# untitled.net
KiCad netlist of a schematic drawn in EAGLE
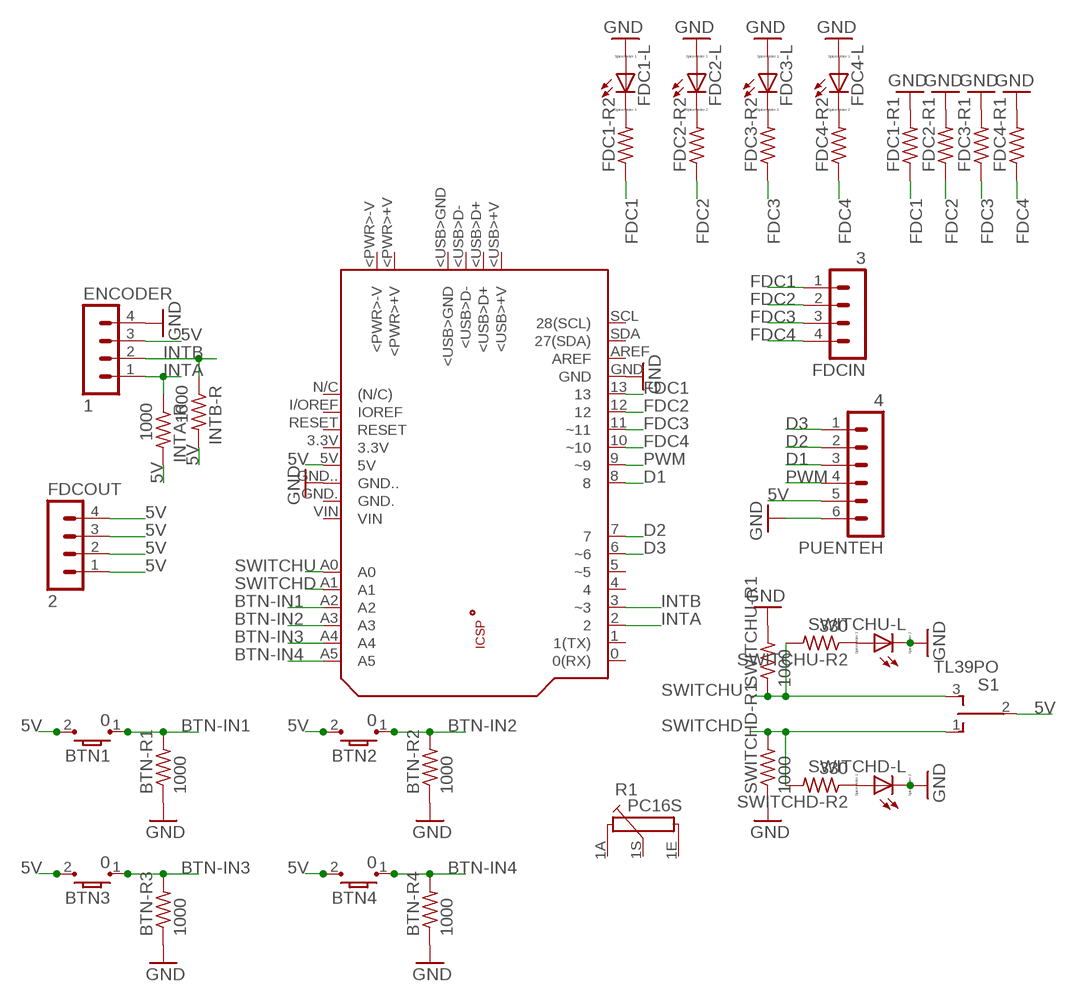
[diagram p0: schematic, sheet 1]

(export (version "E")
  (design (tool "Eeschema 10.0.6"))
  (components
    (comp (ref "BTN-R1")
      (value "1000")
      (footprint "eagle-import:0204_7")
      (libsource (lib "eagle-import") (part "R-US_0204/7"))
    )
    (comp (ref "BTN-R2")
      (value "1000")
      (footprint "eagle-import:0204_7")
      (libsource (lib "eagle-import") (part "R-US_0204/7"))
    )
    (comp (ref "BTN-R3")
      (value "1000")
      (footprint "eagle-import:0204_7")
      (libsource (lib "eagle-import") (part "R-US_0204/7"))
    )
    (comp (ref "BTN-R4")
      (value "1000")
      (footprint "eagle-import:0204_7")
      (libsource (lib "eagle-import") (part "R-US_0204/7"))
    )
    (comp (ref "BTN1")
      (value "0")
      (footprint "eagle-import:TL3303_J")
      (libsource (lib "eagle-import") (part "TL3302-J"))
    )
    (comp (ref "BTN2")
      (value "0")
      (footprint "eagle-import:TL3303_J")
      (libsource (lib "eagle-import") (part "TL3302-J"))
    )
    (comp (ref "BTN3")
      (value "0")
      (footprint "eagle-import:TL3303_J")
      (libsource (lib "eagle-import") (part "TL3302-J"))
    )
    (comp (ref "BTN4")
      (value "0")
      (footprint "eagle-import:TL3303_J")
      (libsource (lib "eagle-import") (part "TL3302-J"))
    )
    (comp (ref "ENCODER")
      (value "1")
      (footprint "eagle-import:MA04-1")
      (libsource (lib "eagle-import") (part "MA04-1"))
    )
    (comp (ref "FDC1-L")
      (value "LED_ELD260")
      (footprint "eagle-import:LED_LD260")
      (libsource (lib "eagle-import") (part "LED_ELD260"))
    )
    (comp (ref "FDC1-R1")
      (value "R-US_0204/7")
      (footprint "eagle-import:0204_7")
      (libsource (lib "eagle-import") (part "R-US_0204/7"))
    )
    (comp (ref "FDC1-R2")
      (value "R-US_0204/7")
      (footprint "eagle-import:0204_7")
      (libsource (lib "eagle-import") (part "R-US_0204/7"))
    )
    (comp (ref "FDC2-L")
      (value "LED_ELD260")
      (footprint "eagle-import:LED_LD260")
      (libsource (lib "eagle-import") (part "LED_ELD260"))
    )
    (comp (ref "FDC2-R1")
      (value "R-US_0204/7")
      (footprint "eagle-import:0204_7")
      (libsource (lib "eagle-import") (part "R-US_0204/7"))
    )
    (comp (ref "FDC2-R2")
      (value "R-US_0204/7")
      (footprint "eagle-import:0204_7")
      (libsource (lib "eagle-import") (part "R-US_0204/7"))
    )
    (comp (ref "FDC3-L")
      (value "LED_ELD260")
      (footprint "eagle-import:LED_LD260")
      (libsource (lib "eagle-import") (part "LED_ELD260"))
    )
    (comp (ref "FDC3-R1")
      (value "R-US_0204/7")
      (footprint "eagle-import:0204_7")
      (libsource (lib "eagle-import") (part "R-US_0204/7"))
    )
    (comp (ref "FDC3-R2")
      (value "R-US_0204/7")
      (footprint "eagle-import:0204_7")
      (libsource (lib "eagle-import") (part "R-US_0204/7"))
    )
    (comp (ref "FDC4-L")
      (value "LED_ELD260")
      (footprint "eagle-import:LED_LD260")
      (libsource (lib "eagle-import") (part "LED_ELD260"))
    )
    (comp (ref "FDC4-R1")
      (value "R-US_0204/7")
      (footprint "eagle-import:0204_7")
      (libsource (lib "eagle-import") (part "R-US_0204/7"))
    )
    (comp (ref "FDC4-R2")
      (value "R-US_0204/7")
      (footprint "eagle-import:0204_7")
      (libsource (lib "eagle-import") (part "R-US_0204/7"))
    )
    (comp (ref "FDCIN")
      (value "3")
      (footprint "eagle-import:MA04-1")
      (libsource (lib "eagle-import") (part "MA04-1"))
    )
    (comp (ref "FDCOUT")
      (value "2")
      (footprint "eagle-import:MA04-1")
      (libsource (lib "eagle-import") (part "MA04-1"))
    )
    (comp (ref "INTA-R")
      (value "1000")
      (footprint "eagle-import:0204_7")
      (libsource (lib "eagle-import") (part "R-US_0204/7"))
    )
    (comp (ref "INTB-R")
      (value "1000")
      (footprint "eagle-import:0204_7")
      (libsource (lib "eagle-import") (part "R-US_0204/7"))
    )
    (comp (ref "PCB1")
      (value "ARDUINO_UNO")
      (footprint "eagle-import:ARDUINO_UNO")
      (libsource (lib "eagle-import") (part "ARDUINO_UNO"))
    )
    (comp (ref "PUENTEH")
      (value "4")
      (footprint "eagle-import:MA06-1")
      (libsource (lib "eagle-import") (part "MA06-1"))
    )
    (comp (ref "R1")
      (value "PC16S")
      (footprint "eagle-import:PC16S")
      (libsource (lib "eagle-import") (part "PC16S"))
    )
    (comp (ref "S1")
      (value "TL39PO")
      (footprint "eagle-import:TL3XPO")
      (libsource (lib "eagle-import") (part "TL39PO"))
    )
    (comp (ref "SWITCHD-L")
      (value "LED_ELD260")
      (footprint "eagle-import:LED_LD260")
      (libsource (lib "eagle-import") (part "LED_ELD260"))
    )
    (comp (ref "SWITCHD-R1")
      (value "1000")
      (footprint "eagle-import:0204_7")
      (libsource (lib "eagle-import") (part "R-US_0204/7"))
    )
    (comp (ref "SWITCHD-R2")
      (value "330")
      (footprint "eagle-import:0204_7")
      (libsource (lib "eagle-import") (part "R-US_0204/7"))
    )
    (comp (ref "SWITCHU-L")
      (value "LED_ELD260")
      (footprint "eagle-import:LED_LD260")
      (libsource (lib "eagle-import") (part "LED_ELD260"))
    )
    (comp (ref "SWITCHU-R1")
      (value "1000")
      (footprint "eagle-import:0204_7")
      (libsource (lib "eagle-import") (part "R-US_0204/7"))
    )
    (comp (ref "SWITCHU-R2")
      (value "330")
      (footprint "eagle-import:0204_7")
      (libsource (lib "eagle-import") (part "R-US_0204/7"))
    )
  )
  (nets
    (net (code "1") (name "/5V") (class "Default")
      (node (ref "BTN1") (pin "2") (pinfunction "2_2") (pintype "passive"))
      (node (ref "BTN2") (pin "2") (pinfunction "2_2") (pintype "passive"))
      (node (ref "BTN3") (pin "2") (pinfunction "2_2") (pintype "passive"))
      (node (ref "BTN4") (pin "2") (pinfunction "2_2") (pintype "passive"))
      (node (ref "ENCODER") (pin "3") (pinfunction "3_3") (pintype "passive"))
      (node (ref "FDCOUT") (pin "1") (pinfunction "1_1") (pintype "passive"))
      (node (ref "FDCOUT") (pin "2") (pinfunction "2_2") (pintype "passive"))
      (node (ref "FDCOUT") (pin "3") (pinfunction "3_3") (pintype "passive"))
      (node (ref "FDCOUT") (pin "4") (pinfunction "4_4") (pintype "passive"))
      (node (ref "INTA-R") (pin "2") (pinfunction "2_2") (pintype "passive"))
      (node (ref "INTB-R") (pin "2") (pinfunction "2_2") (pintype "passive"))
      (node (ref "PCB1") (pin "5V") (pinfunction "5V_5V") (pintype "bidirectional"))
      (node (ref "PUENTEH") (pin "5") (pinfunction "5_5") (pintype "passive"))
      (node (ref "S1") (pin "2") (pinfunction "P_2") (pintype "passive"))
    )
    (net (code "2") (name "/BTN-IN1") (class "Default")
      (node (ref "BTN-R1") (pin "2") (pinfunction "2_2") (pintype "passive"))
      (node (ref "BTN1") (pin "1") (pinfunction "1_1") (pintype "passive"))
      (node (ref "PCB1") (pin "A2") (pinfunction "A2_A2") (pintype "bidirectional"))
    )
    (net (code "3") (name "/BTN-IN2") (class "Default")
      (node (ref "BTN-R2") (pin "2") (pinfunction "2_2") (pintype "passive"))
      (node (ref "BTN2") (pin "1") (pinfunction "1_1") (pintype "passive"))
      (node (ref "PCB1") (pin "A3") (pinfunction "A3_A3") (pintype "bidirectional"))
    )
    (net (code "4") (name "/BTN-IN3") (class "Default")
      (node (ref "BTN-R3") (pin "2") (pinfunction "2_2") (pintype "passive"))
      (node (ref "BTN3") (pin "1") (pinfunction "1_1") (pintype "passive"))
      (node (ref "PCB1") (pin "A4") (pinfunction "A4_A4") (pintype "bidirectional"))
    )
    (net (code "5") (name "/BTN-IN4") (class "Default")
      (node (ref "BTN-R4") (pin "2") (pinfunction "2_2") (pintype "passive"))
      (node (ref "BTN4") (pin "1") (pinfunction "1_1") (pintype "passive"))
      (node (ref "PCB1") (pin "A5") (pinfunction "A5_A5") (pintype "bidirectional"))
    )
    (net (code "6") (name "/D1") (class "Default")
      (node (ref "PCB1") (pin "8") (pinfunction "8_8") (pintype "bidirectional"))
      (node (ref "PUENTEH") (pin "3") (pinfunction "3_3") (pintype "passive"))
    )
    (net (code "7") (name "/D2") (class "Default")
      (node (ref "PCB1") (pin "7") (pinfunction "7_7") (pintype "bidirectional"))
      (node (ref "PUENTEH") (pin "2") (pinfunction "2_2") (pintype "passive"))
    )
    (net (code "8") (name "/D3") (class "Default")
      (node (ref "PCB1") (pin "6") (pinfunction "~{6}_6") (pintype "bidirectional"))
      (node (ref "PUENTEH") (pin "1") (pinfunction "1_1") (pintype "passive"))
    )
    (net (code "9") (name "/FDC1") (class "Default")
      (node (ref "FDC1-R1") (pin "1") (pinfunction "1_1") (pintype "passive"))
      (node (ref "FDC1-R2") (pin "1") (pinfunction "1_1") (pintype "passive"))
      (node (ref "FDCIN") (pin "1") (pinfunction "1_1") (pintype "passive"))
      (node (ref "PCB1") (pin "13") (pinfunction "13_13") (pintype "bidirectional"))
    )
    (net (code "10") (name "/FDC2") (class "Default")
      (node (ref "FDC2-R1") (pin "1") (pinfunction "1_1") (pintype "passive"))
      (node (ref "FDC2-R2") (pin "1") (pinfunction "1_1") (pintype "passive"))
      (node (ref "FDCIN") (pin "2") (pinfunction "2_2") (pintype "passive"))
      (node (ref "PCB1") (pin "12") (pinfunction "12_12") (pintype "bidirectional"))
    )
    (net (code "11") (name "/FDC3") (class "Default")
      (node (ref "FDC3-R1") (pin "1") (pinfunction "1_1") (pintype "passive"))
      (node (ref "FDC3-R2") (pin "1") (pinfunction "1_1") (pintype "passive"))
      (node (ref "FDCIN") (pin "3") (pinfunction "3_3") (pintype "passive"))
      (node (ref "PCB1") (pin "11") (pinfunction "~{11}_11") (pintype "bidirectional"))
    )
    (net (code "12") (name "/FDC4") (class "Default")
      (node (ref "FDC4-R1") (pin "1") (pinfunction "1_1") (pintype "passive"))
      (node (ref "FDC4-R2") (pin "1") (pinfunction "1_1") (pintype "passive"))
      (node (ref "FDCIN") (pin "4") (pinfunction "4_4") (pintype "passive"))
      (node (ref "PCB1") (pin "10") (pinfunction "~{10}_10") (pintype "bidirectional"))
    )
    (net (code "13") (name "/INTA") (class "Default")
      (node (ref "ENCODER") (pin "1") (pinfunction "1_1") (pintype "passive"))
      (node (ref "INTA-R") (pin "1") (pinfunction "1_1") (pintype "passive"))
      (node (ref "PCB1") (pin "2") (pinfunction "2_2") (pintype "bidirectional"))
    )
    (net (code "14") (name "/INTB") (class "Default")
      (node (ref "ENCODER") (pin "2") (pinfunction "2_2") (pintype "passive"))
      (node (ref "INTB-R") (pin "1") (pinfunction "1_1") (pintype "passive"))
      (node (ref "PCB1") (pin "3") (pinfunction "~{3}_3") (pintype "bidirectional"))
    )
    (net (code "15") (name "/PWM") (class "Default")
      (node (ref "PCB1") (pin "9") (pinfunction "~{9}_9") (pintype "bidirectional"))
      (node (ref "PUENTEH") (pin "4") (pinfunction "4_4") (pintype "passive"))
    )
    (net (code "16") (name "/SWITCHD") (class "Default")
      (node (ref "PCB1") (pin "A1") (pinfunction "A1_A1") (pintype "bidirectional"))
      (node (ref "S1") (pin "1") (pinfunction "O_1") (pintype "passive"))
      (node (ref "SWITCHD-R1") (pin "2") (pinfunction "2_2") (pintype "passive"))
      (node (ref "SWITCHD-R2") (pin "2") (pinfunction "2_2") (pintype "passive"))
    )
    (net (code "17") (name "/SWITCHU") (class "Default")
      (node (ref "PCB1") (pin "A0") (pinfunction "A0_A0") (pintype "bidirectional"))
      (node (ref "S1") (pin "3") (pinfunction "S_3") (pintype "passive"))
      (node (ref "SWITCHU-R1") (pin "1") (pinfunction "1_1") (pintype "passive"))
      (node (ref "SWITCHU-R2") (pin "2") (pinfunction "2_2") (pintype "passive"))
    )
    (net (code "18") (name "GND") (class "Default")
      (node (ref "BTN-R1") (pin "1") (pinfunction "1_1") (pintype "passive"))
      (node (ref "BTN-R2") (pin "1") (pinfunction "1_1") (pintype "passive"))
      (node (ref "BTN-R3") (pin "1") (pinfunction "1_1") (pintype "passive"))
      (node (ref "BTN-R4") (pin "1") (pinfunction "1_1") (pintype "passive"))
      (node (ref "ENCODER") (pin "4") (pinfunction "4_4") (pintype "passive"))
      (node (ref "FDC1-L") (pin "A") (pinfunction "A_A") (pintype "passive"))
      (node (ref "FDC1-R1") (pin "2") (pinfunction "2_2") (pintype "passive"))
      (node (ref "FDC2-L") (pin "A") (pinfunction "A_A") (pintype "passive"))
      (node (ref "FDC2-R1") (pin "2") (pinfunction "2_2") (pintype "passive"))
      (node (ref "FDC3-L") (pin "A") (pinfunction "A_A") (pintype "passive"))
      (node (ref "FDC3-R1") (pin "2") (pinfunction "2_2") (pintype "passive"))
      (node (ref "FDC4-L") (pin "A") (pinfunction "A_A") (pintype "passive"))
      (node (ref "FDC4-R1") (pin "2") (pinfunction "2_2") (pintype "passive"))
      (node (ref "PCB1") (pin "GND") (pinfunction "GND_GND") (pintype "bidirectional"))
      (node (ref "PCB1") (pin "GND..") (pinfunction "GND.._GND..") (pintype "bidirectional"))
      (node (ref "PUENTEH") (pin "6") (pinfunction "6_6") (pintype "passive"))
      (node (ref "SWITCHD-L") (pin "K") (pinfunction "C_K") (pintype "passive"))
      (node (ref "SWITCHD-R1") (pin "1") (pinfunction "1_1") (pintype "passive"))
      (node (ref "SWITCHU-L") (pin "K") (pinfunction "C_K") (pintype "passive"))
      (node (ref "SWITCHU-R1") (pin "2") (pinfunction "2_2") (pintype "passive"))
    )
    (net (code "19") (name "Net-(FDC1-L-C)") (class "Default")
      (node (ref "FDC1-L") (pin "K") (pinfunction "C_K") (pintype "passive"))
      (node (ref "FDC1-R2") (pin "2") (pinfunction "2_2") (pintype "passive"))
    )
    (net (code "20") (name "Net-(FDC2-L-C)") (class "Default")
      (node (ref "FDC2-L") (pin "K") (pinfunction "C_K") (pintype "passive"))
      (node (ref "FDC2-R2") (pin "2") (pinfunction "2_2") (pintype "passive"))
    )
    (net (code "21") (name "Net-(FDC3-L-C)") (class "Default")
      (node (ref "FDC3-L") (pin "K") (pinfunction "C_K") (pintype "passive"))
      (node (ref "FDC3-R2") (pin "2") (pinfunction "2_2") (pintype "passive"))
    )
    (net (code "22") (name "Net-(FDC4-L-C)") (class "Default")
      (node (ref "FDC4-L") (pin "K") (pinfunction "C_K") (pintype "passive"))
      (node (ref "FDC4-R2") (pin "2") (pinfunction "2_2") (pintype "passive"))
    )
    (net (code "23") (name "Net-(SWITCHD-L-PadA)") (class "Default")
      (node (ref "SWITCHD-L") (pin "A") (pinfunction "A_A") (pintype "passive"))
      (node (ref "SWITCHD-R2") (pin "1") (pinfunction "1_1") (pintype "passive"))
    )
    (net (code "24") (name "Net-(SWITCHU-L-PadA)") (class "Default")
      (node (ref "SWITCHU-L") (pin "A") (pinfunction "A_A") (pintype "passive"))
      (node (ref "SWITCHU-R2") (pin "1") (pinfunction "1_1") (pintype "passive"))
    )
    (net (code "25") (name "unconnected-(PCB1-(N{slash}C)-PadN{slash}C)") (class "Default")
      (node (ref "PCB1") (pin "N/C") (pinfunction "(N/C)_N/C") (pintype "bidirectional"))
    )
    (net (code "26") (name "unconnected-(PCB1-0(RX)-Pad0)") (class "Default")
      (node (ref "PCB1") (pin "0") (pinfunction "0(RX)_0") (pintype "bidirectional"))
    )
    (net (code "27") (name "unconnected-(PCB1-1(TX)-Pad1)") (class "Default")
      (node (ref "PCB1") (pin "1") (pinfunction "1(TX)_1") (pintype "bidirectional"))
    )
    (net (code "28") (name "unconnected-(PCB1-27(SDA)-PadSDA)") (class "Default")
      (node (ref "PCB1") (pin "SDA") (pinfunction "27(SDA)_SDA") (pintype "bidirectional"))
    )
    (net (code "29") (name "unconnected-(PCB1-28(SCL)-PadSCL)") (class "Default")
      (node (ref "PCB1") (pin "SCL") (pinfunction "28(SCL)_SCL") (pintype "bidirectional"))
    )
    (net (code "30") (name "unconnected-(PCB1-IOREF-PadI{slash}OREF)") (class "Default")
      (node (ref "PCB1") (pin "I/OREF") (pinfunction "IOREF_I/OREF") (pintype "bidirectional"))
    )
    (net (code "31") (name "unconnected-(PCB1-Pad+5V)") (class "Default")
      (node (ref "PCB1") (pin "+5V") (pinfunction "+5V_+5V") (pintype "bidirectional"))
    )
    (net (code "32") (name "unconnected-(PCB1-Pad3.3V)") (class "Default")
      (node (ref "PCB1") (pin "3.3V") (pinfunction "3.3V_3.3V") (pintype "bidirectional"))
    )
    (net (code "33") (name "unconnected-(PCB1-Pad4)") (class "Default")
      (node (ref "PCB1") (pin "4") (pinfunction "4_4") (pintype "bidirectional"))
    )
    (net (code "34") (name "unconnected-(PCB1-Pad<PWR>+V)") (class "Default")
      (node (ref "PCB1") (pin "<PWR>+V") (pinfunction "<PWR>+V_<PWR>+V") (pintype "bidirectional"))
    )
    (net (code "35") (name "unconnected-(PCB1-Pad<PWR>-V)") (class "Default")
      (node (ref "PCB1") (pin "<PWR>-V") (pinfunction "<PWR>-V_<PWR>-V") (pintype "bidirectional"))
    )
    (net (code "36") (name "unconnected-(PCB1-Pad<USB>+V)") (class "Default")
      (node (ref "PCB1") (pin "<USB>+V") (pinfunction "<USB>+V_<USB>+V") (pintype "bidirectional"))
    )
    (net (code "37") (name "unconnected-(PCB1-Pad<USB>D+)") (class "Default")
      (node (ref "PCB1") (pin "<USB>D+") (pinfunction "<USB>D+_<USB>D+") (pintype "bidirectional"))
    )
    (net (code "38") (name "unconnected-(PCB1-Pad<USB>D-)") (class "Default")
      (node (ref "PCB1") (pin "<USB>D-") (pinfunction "<USB>D-_<USB>D-") (pintype "bidirectional"))
    )
    (net (code "39") (name "unconnected-(PCB1-Pad<USB>GND)") (class "Default")
      (node (ref "PCB1") (pin "<USB>GND") (pinfunction "<USB>GND_<USB>GND") (pintype "bidirectional"))
    )
    (net (code "40") (name "unconnected-(PCB1-PadAREF)") (class "Default")
      (node (ref "PCB1") (pin "AREF") (pinfunction "AREF_AREF") (pintype "bidirectional"))
    )
    (net (code "41") (name "unconnected-(PCB1-PadGND.)") (class "Default")
      (node (ref "PCB1") (pin "GND.") (pinfunction "GND._GND.") (pintype "bidirectional"))
    )
    (net (code "42") (name "unconnected-(PCB1-PadGND_)") (class "Default")
      (node (ref "PCB1") (pin "GND_") (pinfunction "GND__GND_") (pintype "bidirectional"))
    )
    (net (code "43") (name "unconnected-(PCB1-PadMISO)") (class "Default")
      (node (ref "PCB1") (pin "MISO") (pinfunction "MISO_MISO") (pintype "bidirectional"))
    )
    (net (code "44") (name "unconnected-(PCB1-PadMOSI)") (class "Default")
      (node (ref "PCB1") (pin "MOSI") (pinfunction "MOSI_MOSI") (pintype "bidirectional"))
    )
    (net (code "45") (name "unconnected-(PCB1-PadRESET)") (class "Default")
      (node (ref "PCB1") (pin "RESET") (pinfunction "RESET_RESET") (pintype "bidirectional"))
    )
    (net (code "46") (name "unconnected-(PCB1-PadRESET.)") (class "Default")
      (node (ref "PCB1") (pin "RESET.") (pinfunction "RESET._RESET.") (pintype "bidirectional"))
    )
    (net (code "47") (name "unconnected-(PCB1-PadSCK)") (class "Default")
      (node (ref "PCB1") (pin "SCK") (pinfunction "SCK_SCK") (pintype "bidirectional"))
    )
    (net (code "48") (name "unconnected-(PCB1-PadVIN)") (class "Default")
      (node (ref "PCB1") (pin "VIN") (pinfunction "VIN_VIN") (pintype "bidirectional"))
    )
    (net (code "49") (name "unconnected-(PCB1-~{5}-Pad5)") (class "Default")
      (node (ref "PCB1") (pin "5") (pinfunction "~{5}_5") (pintype "bidirectional"))
    )
    (net (code "50") (name "unconnected-(R1-Pad1A)") (class "Default")
      (node (ref "R1") (pin "1A") (pinfunction "1A_1A") (pintype "passive"))
    )
    (net (code "51") (name "unconnected-(R1-Pad1E)") (class "Default")
      (node (ref "R1") (pin "1E") (pinfunction "1E_1E") (pintype "passive"))
    )
    (net (code "52") (name "unconnected-(R1-Pad1S)") (class "Default")
      (node (ref "R1") (pin "1S") (pinfunction "1S_1S") (pintype "passive"))
    )
  )
)
